# Receive_config.net
KiCad netlist of a schematic drawn in Altium Designer
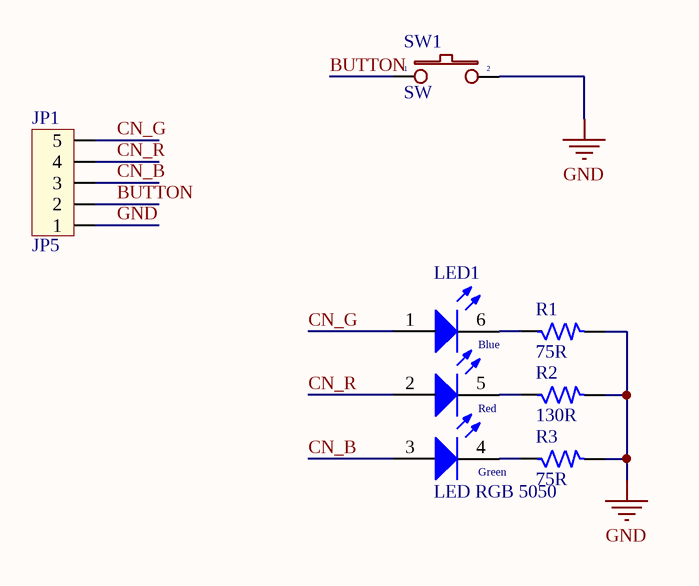
[diagram p0: Receive config.SchDoc]

(export (version "E")
  (design (tool "Eeschema 10.0.6"))
  (components
    (comp (ref "JP1")
      (value "JP5")
      (footprint "XH2.54-5P")
      (description "Connector 5")
      (libsource (lib "Thu Vien Chuan") (part "Header 5P"))
    )
    (comp (ref "LED1")
      (value "LED RGB 5050")
      (footprint "LED RGB 5050")
      (fields
        (field (name "PARTNO") "150141M173100")
        (field (name "MANUFACTURER") "Würth Elektronik eiSos GmbH")
        (field (name "CREATED BY") "Christin Otto")
      )
      (libsource (lib "Thu Vien Chuan") (part "LED RGB 5050"))
    )
    (comp (ref "R1")
      (value "75R")
      (footprint "Thu Vien Chuan :RES-SMD-0805")
      (description "Tro 1/4W")
      (libsource (lib "Thu Vien Chuan") (part "RES 1/4W"))
    )
    (comp (ref "R2")
      (value "130R")
      (footprint "Thu Vien Chuan :RES-SMD-0805")
      (description "Tro 1/4W")
      (libsource (lib "Thu Vien Chuan") (part "RES 1/4W"))
    )
    (comp (ref "R3")
      (value "75R")
      (footprint "Thu Vien Chuan :RES-SMD-0805")
      (description "Tro 1/4W")
      (libsource (lib "Thu Vien Chuan") (part "RES 1/4W"))
    )
    (comp (ref "SW1")
      (value "SW")
      (footprint "SW2")
      (description "Switch button 2 pin")
      (libsource (lib "Thu Vien Chuan") (part "SW2"))
    )
  )
  (nets
    (net (code "1") (name "/BUTTON") (class "Default")
      (node (ref "JP1") (pin "2") (pinfunction "2_2") (pintype "passive"))
      (node (ref "SW1") (pin "1") (pinfunction "1_1") (pintype "passive"))
    )
    (net (code "2") (name "/CN_B") (class "Default")
      (node (ref "JP1") (pin "3") (pinfunction "3_3") (pintype "passive"))
      (node (ref "LED1") (pin "3") (pintype "passive"))
    )
    (net (code "3") (name "/CN_G") (class "Default")
      (node (ref "JP1") (pin "5") (pinfunction "5_5") (pintype "passive"))
      (node (ref "LED1") (pin "1") (pintype "passive"))
    )
    (net (code "4") (name "/CN_R") (class "Default")
      (node (ref "JP1") (pin "4") (pinfunction "4_4") (pintype "passive"))
      (node (ref "LED1") (pin "2") (pintype "passive"))
    )
    (net (code "5") (name "GND") (class "Default")
      (node (ref "JP1") (pin "1") (pinfunction "1_1") (pintype "passive"))
      (node (ref "R1") (pin "2") (pinfunction "2_2") (pintype "passive"))
      (node (ref "R2") (pin "2") (pinfunction "2_2") (pintype "passive"))
      (node (ref "R3") (pin "2") (pinfunction "2_2") (pintype "passive"))
      (node (ref "SW1") (pin "2") (pinfunction "2_2") (pintype "passive"))
    )
    (net (code "6") (name "Net-(LED1-Pad4)") (class "Default")
      (node (ref "LED1") (pin "4") (pintype "passive"))
      (node (ref "R3") (pin "1") (pinfunction "1_1") (pintype "passive"))
    )
    (net (code "7") (name "Net-(LED1-Pad5)") (class "Default")
      (node (ref "LED1") (pin "5") (pintype "passive"))
      (node (ref "R2") (pin "1") (pinfunction "1_1") (pintype "passive"))
    )
    (net (code "8") (name "Net-(LED1-Pad6)") (class "Default")
      (node (ref "LED1") (pin "6") (pintype "passive"))
      (node (ref "R1") (pin "1") (pinfunction "1_1") (pintype "passive"))
    )
  )
)
